# Buck_and_LDO.net
KiCad netlist of a schematic drawn in Altium Designer
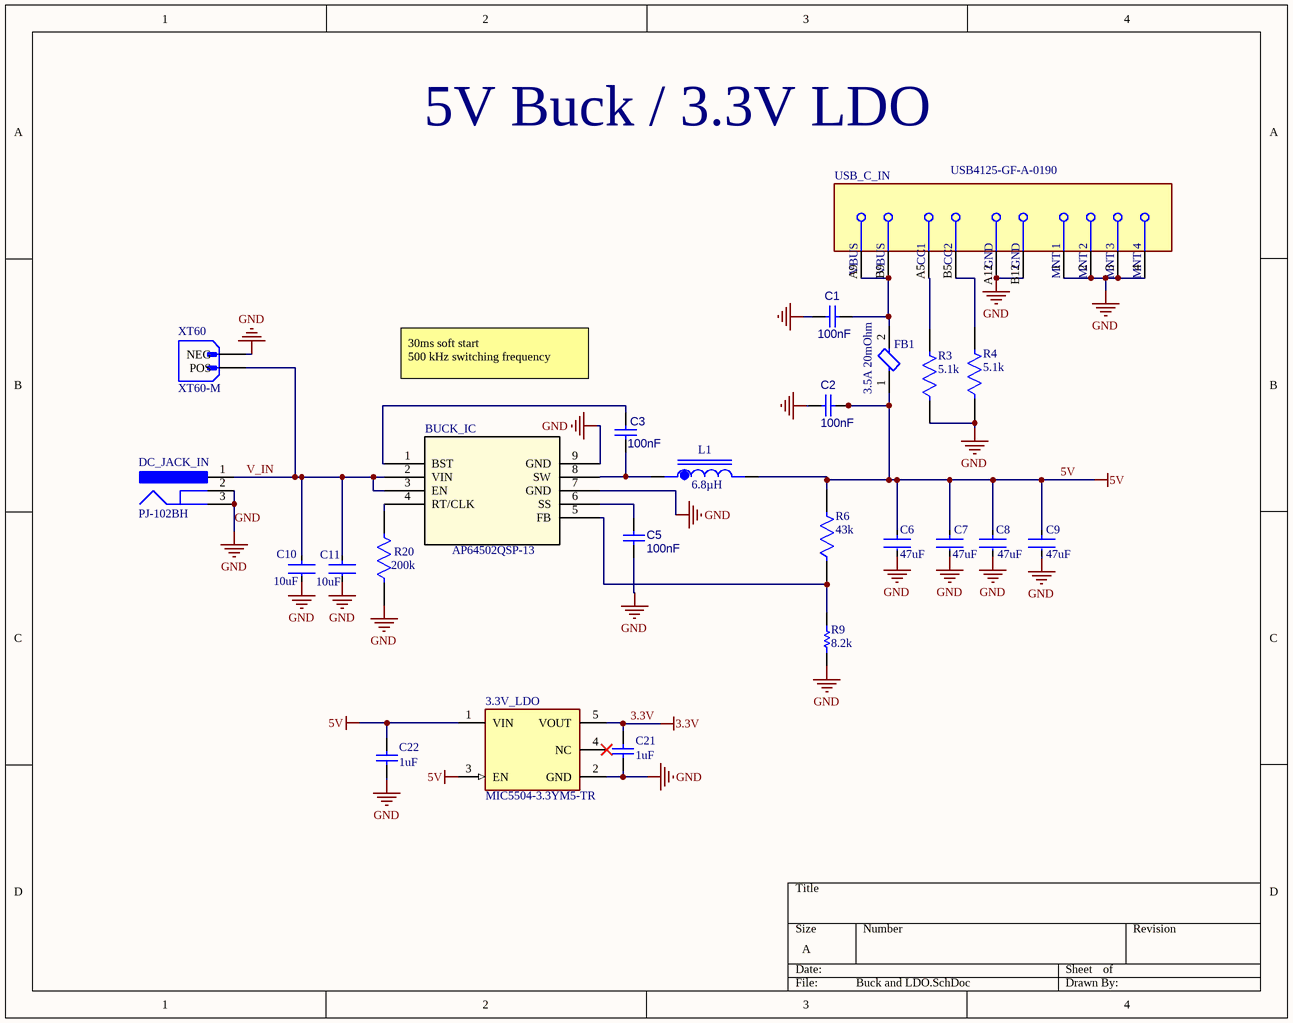
[diagram p0: Buck and LDO.SchDoc]

(export (version "E")
  (design (tool "Eeschema 10.0.6"))
  (components
    (comp (ref "3.3V_LDO")
      (value "MIC5504-3.3YM5-TR")
      (footprint "FP-SOT23-5LD-PL-1-MFG")
      (description "IC REG LINEAR 3.3V 300MA SOT23-5")
      (libsource (lib "Altium Content Vault") (part "96048095611b4a9579e1e315950d302"))
    )
    (comp (ref "BUCK_IC")
      (value "AP64502QSP-13")
      (footprint "SO-8EP_DIO")
      (description "Description")
      (fields (field (name "COPYRIGHT") "Copyright (C) 2025 Ultra Librarian. All rights reserved."))
      (libsource (lib "AP64502QSP-13") (part "AP64502QSP-13"))
    )
    (comp (ref "C1")
      (value "100nF")
      (footprint "CAPC2013X95X50LL10T25")
      (description "Capacitor 100 nF +/-10% 50 V 0805")
      (fields (field (name "TOLERANCE") "10%"))
      (libsource (lib "gugan Sivakumar") (part "CAP-NP-2"))
    )
    (comp (ref "C2")
      (value "100nF")
      (footprint "CAPC2013X95X50LL10T25")
      (description "Capacitor 100 nF +/-10% 50 V 0805")
      (fields (field (name "TOLERANCE") "10%"))
      (libsource (lib "gugan Sivakumar") (part "CAP-NP-2"))
    )
    (comp (ref "C3")
      (value "100nF")
      (footprint "CAPC2013X95X50LL10T25")
      (description "Capacitor 100 nF +/-10% 50 V 0805")
      (fields (field (name "TOLERANCE") "10%"))
      (libsource (lib "gugan Sivakumar") (part "CAP-NP-2"))
    )
    (comp (ref "C5")
      (value "100nF")
      (footprint "CAPC2013X95X50LL10T25")
      (description "Capacitor 100 nF +/-10% 50 V 0805")
      (fields (field (name "TOLERANCE") "10%"))
      (libsource (lib "gugan Sivakumar") (part "CAP-NP-2"))
    )
    (comp (ref "C6")
      (value "47uF")
      (footprint "FP-GRM31C-0_2-e0_3_0_8-IPC_C")
      (description "Chip Multilayer Ceramic Capacitors for General Purpose, 1206, 47uF, X5R, 15%, 20%, 10V")
      (fields (field (name "TOLERANCE") "20%") (field (name "VOLTAGE") "10V"))
      (libsource (lib "Altium Content Vault") (part "02cd4be3c70576c341d710602a673aa"))
    )
    (comp (ref "C7")
      (value "47uF")
      (footprint "FP-GRM31C-0_2-e0_3_0_8-IPC_C")
      (description "Chip Multilayer Ceramic Capacitors for General Purpose, 1206, 47uF, X5R, 15%, 20%, 10V")
      (fields (field (name "TOLERANCE") "20%") (field (name "VOLTAGE") "10V"))
      (libsource (lib "Altium Content Vault") (part "02cd4be3c70576c341d710602a673aa"))
    )
    (comp (ref "C8")
      (value "47uF")
      (footprint "FP-GRM31C-0_2-e0_3_0_8-IPC_C")
      (description "Chip Multilayer Ceramic Capacitors for General Purpose, 1206, 47uF, X5R, 15%, 20%, 10V")
      (fields (field (name "TOLERANCE") "20%") (field (name "VOLTAGE") "10V"))
      (libsource (lib "Altium Content Vault") (part "02cd4be3c70576c341d710602a673aa"))
    )
    (comp (ref "C9")
      (value "47uF")
      (footprint "FP-GRM31C-0_2-e0_3_0_8-IPC_C")
      (description "Chip Multilayer Ceramic Capacitors for General Purpose, 1206, 47uF, X5R, 15%, 20%, 10V")
      (fields (field (name "TOLERANCE") "20%") (field (name "VOLTAGE") "10V"))
      (libsource (lib "Altium Content Vault") (part "02cd4be3c70576c341d710602a673aa"))
    )
    (comp (ref "C10")
      (value "10uF")
      (footprint "FP-CL31-IPC_C")
      (description "CAP CER 10UF 50V X5R 1206")
      (fields (field (name "TOLERANCE") "10%") (field (name "MANUFACTURER") "Samsung"))
      (libsource (lib "Altium Content Vault") (part "11868f565c42a9108669ba33697ecf6"))
    )
    (comp (ref "C11")
      (value "10uF")
      (footprint "FP-CL31-IPC_C")
      (description "CAP CER 10UF 50V X5R 1206")
      (fields (field (name "TOLERANCE") "10%") (field (name "MANUFACTURER") "Samsung"))
      (libsource (lib "Altium Content Vault") (part "11868f565c42a9108669ba33697ecf6"))
    )
    (comp (ref "C21")
      (value "1uF")
      (footprint "CAPC3216X180X50ML20T25")
      (description "Chip Capacitor, 1 uF, +/- 10%, 25 V, -55 to 125 degC, 1206 (3216 Metric), RoHS, Tape and Reel")
      (fields (field (name "MANUFACTURER") "Kemet") (field (name "TOLERANCE") "10%"))
      (libsource (lib "Altium Content Vault") (part "CAP-NP-2"))
    )
    (comp (ref "C22")
      (value "1uF")
      (footprint "CAPC3216X180X50ML20T25")
      (description "Chip Capacitor, 1 uF, +/- 10%, 25 V, -55 to 125 degC, 1206 (3216 Metric), RoHS, Tape and Reel")
      (fields (field (name "MANUFACTURER") "Kemet") (field (name "TOLERANCE") "10%"))
      (libsource (lib "Altium Content Vault") (part "CAP-NP-2"))
    )
    (comp (ref "DC_JACK_IN")
      (value "PJ-102BH")
      (footprint "CUI-PJ-102BH_V")
      (fields (field (name "MANUFACTURER") "CUIInc."))
      (libsource (lib "Altium Content Vault") (part "JACK-2CD3-RN"))
    )
    (comp (ref "FB1")
      (value "3.5A 20mOhm")
      (footprint "FP-BLM31-0_2-t1_1-MFG")
      (description "BLM31PG121SN1L Chip Ferrite Bead Array, 1206, 120Ω @ 100MHz, 0.02Ω, 25%, 3.5A")
      (fields (field (name "TOLERANCE") "25%"))
      (libsource (lib "Altium Content Vault") (part "5f30dd21d616792df468990f7003faa"))
    )
    (comp (ref "L1")
      (value "6.8µH")
      (footprint "IND_MGAH06036R8M-10")
      (description "6.8 ÂµH Shielded Molded Inductor 5 A 50mOhm Max Nonstandard")
      (fields (field (name "MP") "MGAH06036R8M-10") (field (name "MF") "Laird-Signal Integrity Products"))
      (libsource (lib "gugan Sivakumar") (part "MGAH06036R8M-10"))
    )
    (comp (ref "R3")
      (value "5.1k")
      (footprint "FP-MCT0603-IPC_B")
      (description "MCT06030D5101BP500 RES SMD 5100 OHM 1% 1/8W 0603")
      (fields (field (name "TOLERANCE") "0.1%"))
      (libsource (lib "Altium Content Vault") (part "1029c3af85768c4190bb7ad29bc67b5"))
    )
    (comp (ref "R4")
      (value "5.1k")
      (footprint "FP-MCT0603-IPC_B")
      (description "MCT06030D5101BP500 RES SMD 5100 OHM 1% 1/8W 0603")
      (fields (field (name "TOLERANCE") "0.1%"))
      (libsource (lib "Altium Content Vault") (part "1029c3af85768c4190bb7ad29bc67b5"))
    )
    (comp (ref "R6")
      (value "43k")
      (footprint "FP-MCU0805-IPC_C")
      (description "MCU08050C4302FP500 RES 1.05K OHM 0.5% 1/5W 0805")
      (fields (field (name "TOLERANCE") "1%"))
      (libsource (lib "Altium Content Vault") (part "1029c3af85768c4190bb7ad29bc67b5"))
    )
    (comp (ref "R9")
      (value "8.2k")
      (footprint "RESC0805(2012)_N")
      (description "8K2 0.125W 1% 0805 (2012 Metric)  SMD")
      (fields (field (name "POWER") "0.125 W") (field (name "TOLERANCE") "1 %"))
      (libsource (lib "Altium Content Vault") (part "RES"))
    )
    (comp (ref "R20")
      (value "200k")
      (footprint "FP-CRCW0603-HPe3-MFG")
      (description "RES Thick Film, 200kΩ, 1%, 0.33W, 100ppm/°C, 0603")
      (fields (field (name "TOLERANCE") "1%"))
      (libsource (lib "Altium Content Vault") (part "1029c3af85768c4190bb7ad29bc67b5"))
    )
    (comp (ref "USB_C_IN")
      (value "USB4125-GF-A-0190")
      (footprint "FP-USB4125-GF-A-0190-MFG")
      (description "CONN RCPT TYPE C 6P SMD RA")
      (libsource (lib "Altium Content Vault") (part "a055484d46e58b234844902c9fd883a"))
    )
    (comp (ref "XT60")
      (value "XT60-M")
      (footprint "AMASS_XT60-M")
      (description "Plug; DC supply; XT60; male; PIN: 2; for cable; soldered; 30A; 500V")
      (fields (field (name "MF") "AMASS"))
      (libsource (lib "gugan Sivakumar") (part "XT60-M"))
    )
  )
  (nets
    (net (code "1") (name "/V_IN") (class "Default")
      (node (ref "BUCK_IC") (pin "2") (pinfunction "VIN_2") (pintype "passive"))
      (node (ref "BUCK_IC") (pin "3") (pinfunction "EN_3") (pintype "passive"))
      (node (ref "C10") (pin "1") (pinfunction "1_1") (pintype "passive"))
      (node (ref "C11") (pin "1") (pinfunction "1_1") (pintype "passive"))
      (node (ref "DC_JACK_IN") (pin "1") (pinfunction "1_1") (pintype "passive"))
      (node (ref "XT60") (pin "P") (pinfunction "POS_P") (pintype "passive"))
    )
    (net (code "2") (name "3.3V") (class "Default")
      (node (ref "3.3V_LDO") (pin "5") (pinfunction "VOUT_5") (pintype "power_in"))
      (node (ref "C21") (pin "2") (pinfunction "2_2") (pintype "passive"))
    )
    (net (code "3") (name "5V") (class "Default")
      (node (ref "3.3V_LDO") (pin "1") (pinfunction "VIN_1") (pintype "power_in"))
      (node (ref "3.3V_LDO") (pin "3") (pinfunction "EN_3") (pintype "input"))
      (node (ref "C2") (pin "2") (pinfunction "2_2") (pintype "passive"))
      (node (ref "C22") (pin "2") (pinfunction "2_2") (pintype "passive"))
      (node (ref "C6") (pin "1") (pinfunction "1_1") (pintype "passive"))
      (node (ref "C7") (pin "1") (pinfunction "1_1") (pintype "passive"))
      (node (ref "C8") (pin "1") (pinfunction "1_1") (pintype "passive"))
      (node (ref "C9") (pin "1") (pinfunction "1_1") (pintype "passive"))
      (node (ref "FB1") (pin "1") (pinfunction "1_1") (pintype "passive"))
      (node (ref "L1") (pin "2") (pinfunction "2_2") (pintype "passive"))
      (node (ref "R6") (pin "2") (pinfunction "2_2") (pintype "passive"))
    )
    (net (code "4") (name "GND") (class "Default")
      (node (ref "3.3V_LDO") (pin "2") (pinfunction "GND_2") (pintype "power_in"))
      (node (ref "BUCK_IC") (pin "7") (pinfunction "GND_7") (pintype "passive"))
      (node (ref "BUCK_IC") (pin "9") (pinfunction "GND_9") (pintype "passive"))
      (node (ref "C1") (pin "1") (pinfunction "1_1") (pintype "passive"))
      (node (ref "C10") (pin "2") (pinfunction "2_2") (pintype "passive"))
      (node (ref "C11") (pin "2") (pinfunction "2_2") (pintype "passive"))
      (node (ref "C2") (pin "1") (pinfunction "1_1") (pintype "passive"))
      (node (ref "C21") (pin "1") (pinfunction "1_1") (pintype "passive"))
      (node (ref "C22") (pin "1") (pinfunction "1_1") (pintype "passive"))
      (node (ref "C5") (pin "1") (pinfunction "1_1") (pintype "passive"))
      (node (ref "C6") (pin "2") (pinfunction "2_2") (pintype "passive"))
      (node (ref "C7") (pin "2") (pinfunction "2_2") (pintype "passive"))
      (node (ref "C8") (pin "2") (pinfunction "2_2") (pintype "passive"))
      (node (ref "C9") (pin "2") (pinfunction "2_2") (pintype "passive"))
      (node (ref "DC_JACK_IN") (pin "2") (pinfunction "2_2") (pintype "passive"))
      (node (ref "DC_JACK_IN") (pin "3") (pinfunction "3_3") (pintype "passive"))
      (node (ref "R20") (pin "1") (pinfunction "1_1") (pintype "passive"))
      (node (ref "R3") (pin "1") (pinfunction "1_1") (pintype "passive"))
      (node (ref "R4") (pin "1") (pinfunction "1_1") (pintype "passive"))
      (node (ref "R9") (pin "1") (pinfunction "1_1") (pintype "passive"))
      (node (ref "USB_C_IN") (pin "1") (pinfunction "MNT_1_1") (pintype "passive"))
      (node (ref "USB_C_IN") (pin "2") (pinfunction "MNT_2_2") (pintype "passive"))
      (node (ref "USB_C_IN") (pin "3") (pinfunction "MNT_3_3") (pintype "passive"))
      (node (ref "USB_C_IN") (pin "4") (pinfunction "MNT_4_4") (pintype "passive"))
      (node (ref "USB_C_IN") (pin "A12") (pinfunction "GND_A12") (pintype "passive"))
      (node (ref "USB_C_IN") (pin "B12") (pinfunction "GND_B12") (pintype "passive"))
      (node (ref "XT60") (pin "N") (pinfunction "NEG_N") (pintype "passive"))
    )
    (net (code "5") (name "Net-(BUCK_IC-BST)") (class "Default")
      (node (ref "BUCK_IC") (pin "1") (pinfunction "BST_1") (pintype "passive"))
      (node (ref "C3") (pin "2") (pinfunction "2_2") (pintype "passive"))
    )
    (net (code "6") (name "Net-(BUCK_IC-FB)") (class "Default")
      (node (ref "BUCK_IC") (pin "5") (pinfunction "FB_5") (pintype "passive"))
      (node (ref "R6") (pin "1") (pinfunction "1_1") (pintype "passive"))
      (node (ref "R9") (pin "2") (pinfunction "2_2") (pintype "passive"))
    )
    (net (code "7") (name "Net-(BUCK_IC-RT{slash}CLK)") (class "Default")
      (node (ref "BUCK_IC") (pin "4") (pinfunction "RT/CLK_4") (pintype "passive"))
      (node (ref "R20") (pin "2") (pinfunction "2_2") (pintype "passive"))
    )
    (net (code "8") (name "Net-(BUCK_IC-SS)") (class "Default")
      (node (ref "BUCK_IC") (pin "6") (pinfunction "SS_6") (pintype "passive"))
      (node (ref "C5") (pin "2") (pinfunction "2_2") (pintype "passive"))
    )
    (net (code "9") (name "Net-(BUCK_IC-SW)") (class "Default")
      (node (ref "BUCK_IC") (pin "8") (pinfunction "SW_8") (pintype "passive"))
      (node (ref "C3") (pin "1") (pinfunction "1_1") (pintype "passive"))
      (node (ref "L1") (pin "1") (pinfunction "1_1") (pintype "passive"))
    )
    (net (code "10") (name "Net-(C1-Pad2)") (class "Default")
      (node (ref "C1") (pin "2") (pinfunction "2_2") (pintype "passive"))
      (node (ref "FB1") (pin "2") (pinfunction "2_2") (pintype "passive"))
      (node (ref "USB_C_IN") (pin "A9") (pinfunction "VBUS_A9") (pintype "passive"))
      (node (ref "USB_C_IN") (pin "B9") (pinfunction "VBUS_B9") (pintype "passive"))
    )
    (net (code "11") (name "Net-(USB_C_IN-CC1)") (class "Default")
      (node (ref "R3") (pin "2") (pinfunction "2_2") (pintype "passive"))
      (node (ref "USB_C_IN") (pin "A5") (pinfunction "CC1_A5") (pintype "passive"))
    )
    (net (code "12") (name "Net-(USB_C_IN-CC2)") (class "Default")
      (node (ref "R4") (pin "2") (pinfunction "2_2") (pintype "passive"))
      (node (ref "USB_C_IN") (pin "B5") (pinfunction "CC2_B5") (pintype "passive"))
    )
    (net (code "13") (name "unconnected-(3.3V_LDO-NC-Pad4)") (class "Default")
      (node (ref "3.3V_LDO") (pin "4") (pinfunction "NC_4") (pintype "passive+no_connect"))
    )
  )
)
